# ESC_Mounting.net
KiCad netlist of a schematic drawn in Altium Designer
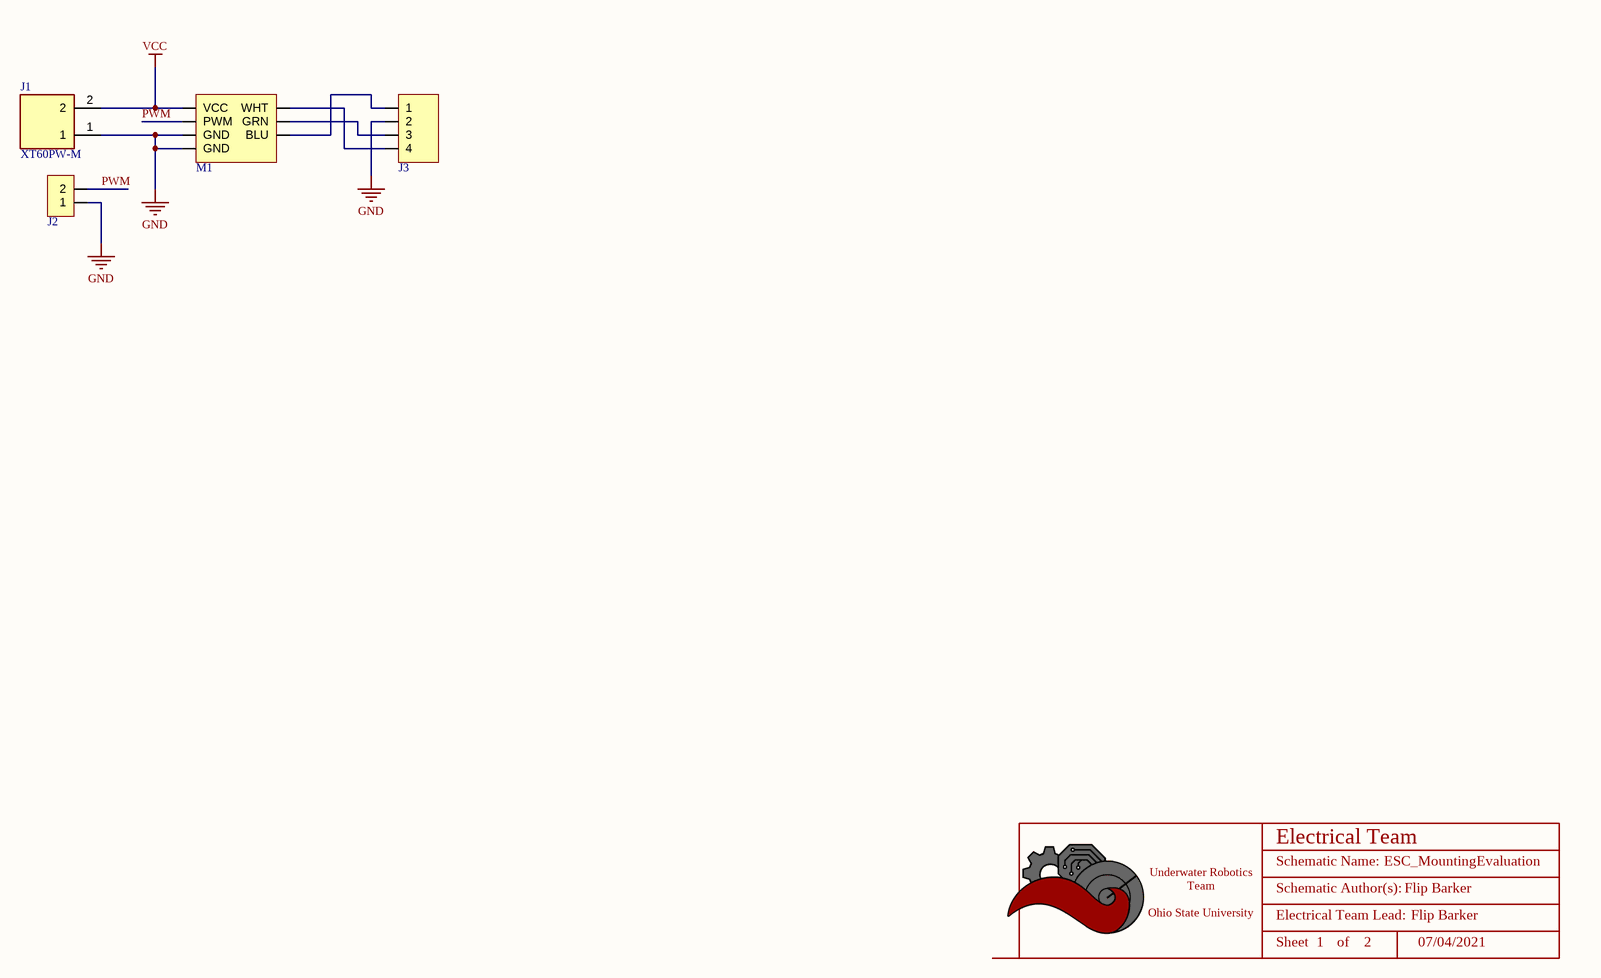
[diagram p0: ESC_Mounting.SchDoc]

(export (version "E")
  (design (tool "Eeschema 10.0.6"))
  (components
    (comp (ref "*")
      (value "Title_Block")
      (description "UWRT Schematic Title Block Template\r\n\r\nCreated June 2021, Dylan Trainor")
      (libsource (lib "Sch_Templates") (part "Title_Block"))
    )
    (comp (ref "J1")
      (value "XT60PW-M")
      (footprint "XT60_PW_AMASS_M")
      (description "XT60 60A Right Angle Male (30-45A MAX)")
      (fields (field (name "MF") "AMASS"))
      (libsource (lib "Connectors") (part "XT60PW-M"))
    )
    (comp (ref "J2")
      (value "2 POS")
      (footprint "HEADER_2PIN_2.54MM")
      (description "CONN HEADER VERT 2POS 2.54MM")
      (fields (field (name "CREATED BY") "Robert P"))
      (libsource (lib "Connectors") (part "HEADER_2PIN_2.54MM"))
    )
    (comp (ref "J3")
      (value "4 POS R/A")
      (footprint "CONN_MOLEX_MINIFIT JR_4 POS_R/A")
      (description "Molex Minifit Jr. 5569 \r\n4 Pos R/A Natural")
      (fields (field (name "MANUFACTURER") "Molex") (field (name "CREATED BY") "Flip B"))
      (libsource (lib "Connectors") (part "CONN_MOLEX_MINIFIT JR_4POS_R/A"))
    )
    (comp (ref "M1")
      (value "Basic ESC")
      (footprint "BASIC_ESC")
      (description "Blue Robotics Basic ESC \r\n7-26V Power, 30A, 5V PWM Signal")
      (fields
        (field (name "VOLTAGE") "7-26V")
        (field (name "MANUFACTURER") "Blue Robotics")
        (field (name "CREATED BY") "Flip B")
      )
      (libsource (lib "Modules") (part "BASIC_ESC"))
    )
  )
  (nets
    (net (code "1") (name "/PWM") (class "Default")
      (node (ref "J2") (pin "2") (pinfunction "2_2") (pintype "passive"))
      (node (ref "M1") (pin "3") (pinfunction "PWM_3") (pintype "passive"))
    )
    (net (code "2") (name "GND") (class "Default")
      (node (ref "J1") (pin "1") (pinfunction "1_1") (pintype "passive"))
      (node (ref "J2") (pin "1") (pinfunction "1_1") (pintype "passive"))
      (node (ref "J3") (pin "2") (pinfunction "2_2") (pintype "passive"))
      (node (ref "M1") (pin "1") (pinfunction "GND_1") (pintype "passive"))
      (node (ref "M1") (pin "2") (pinfunction "GND_2") (pintype "passive"))
    )
    (net (code "3") (name "Net-(M1-BLU)") (class "Default")
      (node (ref "J3") (pin "1") (pinfunction "1_1") (pintype "passive"))
      (node (ref "M1") (pin "5") (pinfunction "BLU_5") (pintype "passive"))
    )
    (net (code "4") (name "Net-(M1-GRN)") (class "Default")
      (node (ref "J3") (pin "3") (pinfunction "3_3") (pintype "passive"))
      (node (ref "M1") (pin "6") (pinfunction "GRN_6") (pintype "passive"))
    )
    (net (code "5") (name "Net-(M1-WHT)") (class "Default")
      (node (ref "J3") (pin "4") (pinfunction "4_4") (pintype "passive"))
      (node (ref "M1") (pin "7") (pinfunction "WHT_7") (pintype "passive"))
    )
    (net (code "6") (name "VCC") (class "Default")
      (node (ref "J1") (pin "2") (pinfunction "2_2") (pintype "passive"))
      (node (ref "M1") (pin "4") (pinfunction "VCC_4") (pintype "passive"))
    )
  )
)
